# APPS.net
KiCad netlist of a schematic drawn in Altium Designer
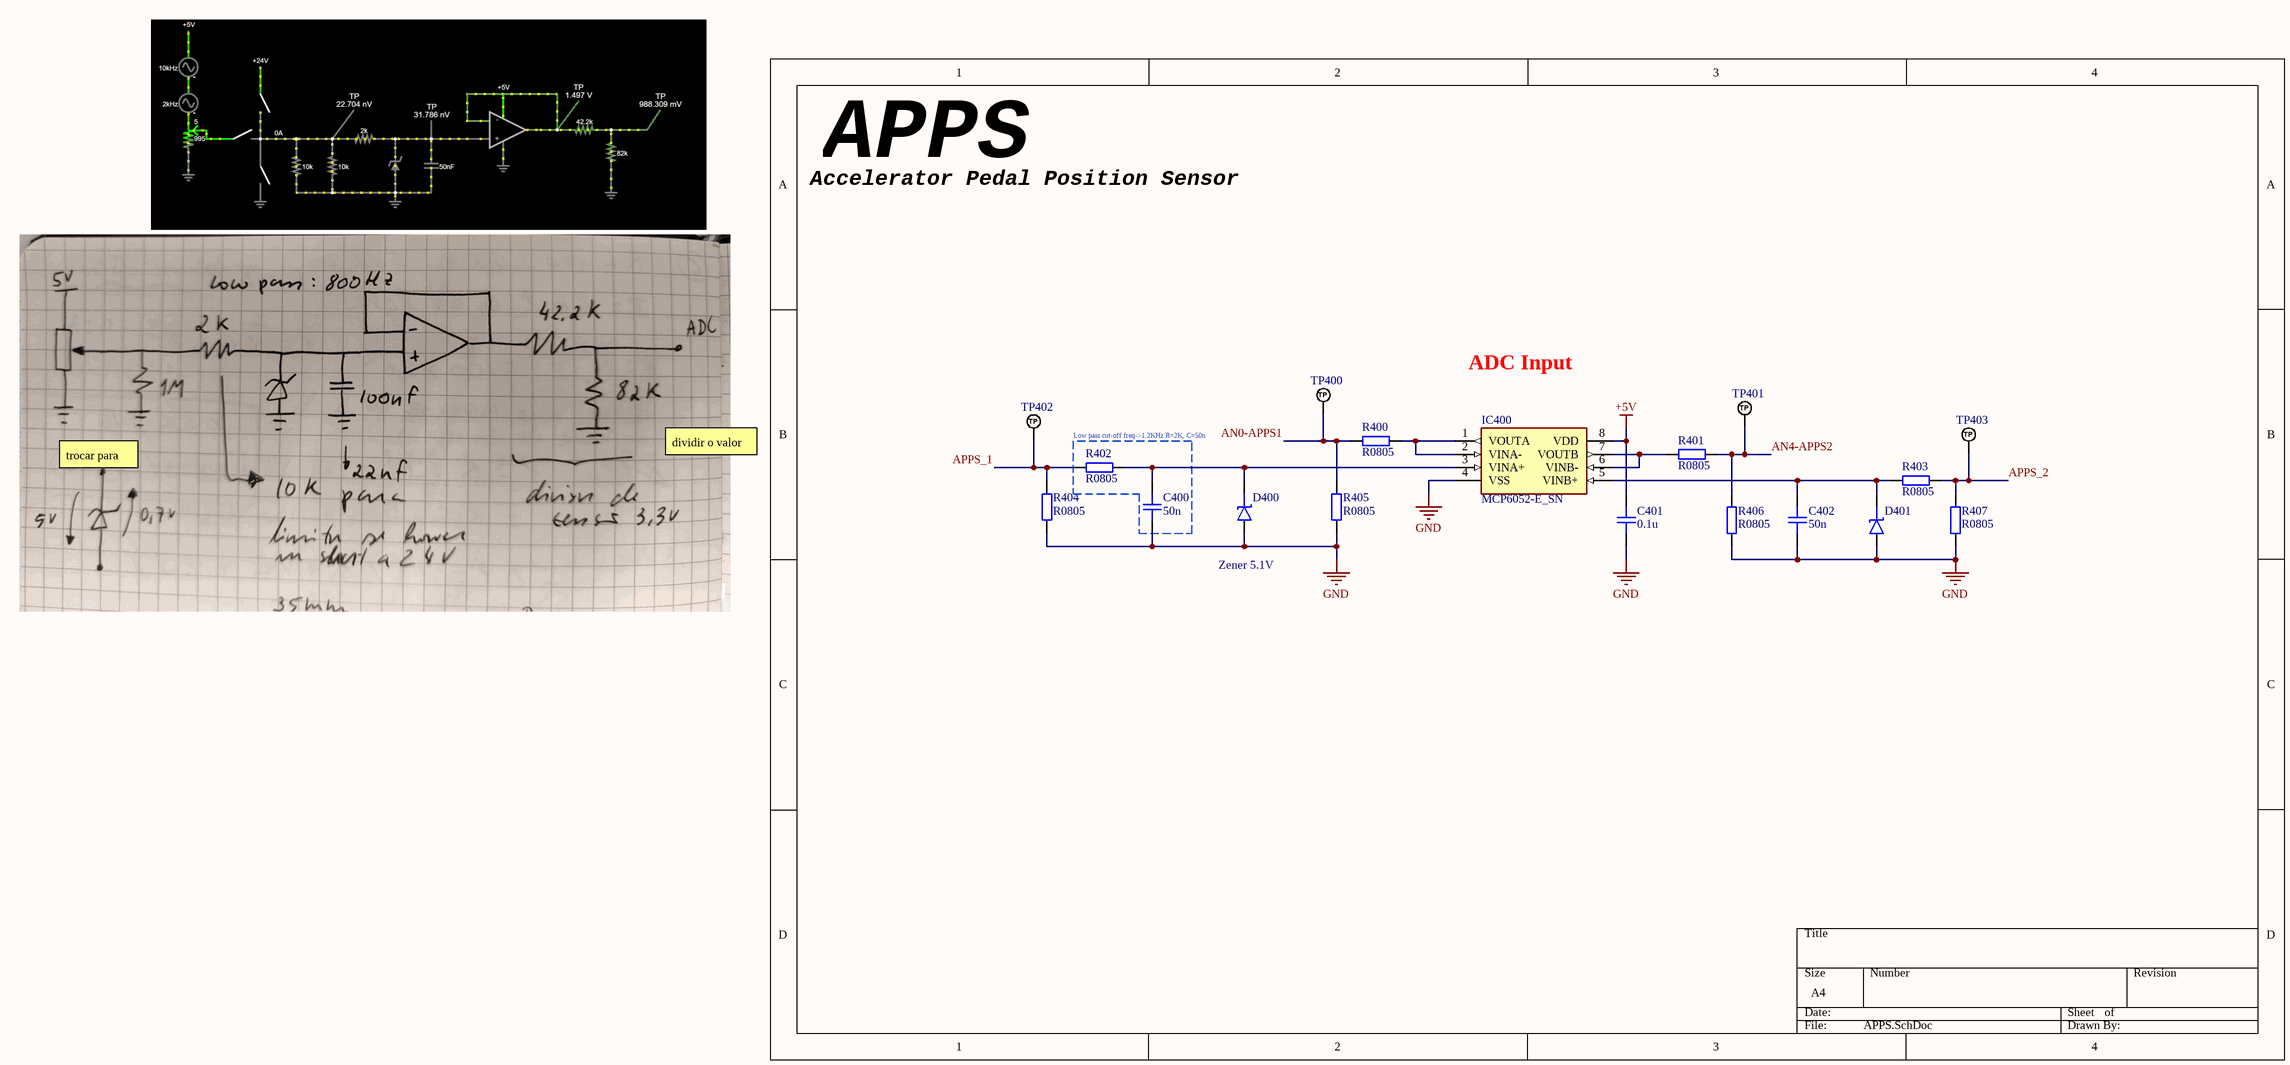
[diagram p0: APPS.SchDoc]

(export (version "E")
  (design (tool "Eeschema 10.0.6"))
  (components
    (comp (ref "C400")
      (value "50n")
      (footprint "CAP_0805")
      (description "Capacitor SMD 0805 10V")
      (libsource (lib "Schematic-Lib-PhilsLab") (part "CAP_0805_10V"))
    )
    (comp (ref "C401")
      (value "0.1u")
      (footprint "CAP_0805")
      (description "Capacitor SMD 0805 10V")
      (libsource (lib "Schematic-Lib-PhilsLab") (part "CAP_0805_10V"))
    )
    (comp (ref "C402")
      (value "50n")
      (footprint "CAP_0805")
      (description "Capacitor SMD 0805 10V")
      (libsource (lib "Schematic-Lib-PhilsLab") (part "CAP_0805_10V"))
    )
    (comp (ref "D400")
      (value "D_SCHOTTKY_SOD_323")
      (footprint "SOD-323")
      (description "Diode Schottky SMD SOD-323")
      (libsource (lib "PhilsLab") (part "D_SCHOTTKY_SOD_323"))
    )
    (comp (ref "D401")
      (value "D_SCHOTTKY_SOD_323")
      (footprint "SOD-323")
      (description "Diode Schottky SMD SOD-323")
      (libsource (lib "PhilsLab") (part "D_SCHOTTKY_SOD_323"))
    )
    (comp (ref "IC400")
      (value "MCP6052-E_SN")
      (footprint "Pedro_pcb_lib:SOIC127P600X175-8N")
      (description "Integrated Circuit")
      (fields
        (field (name "MANUFACTURER_PART_NUMBER") "MCP6052-E/SN")
        (field (name "MOUSER PART NUMBER") "579-MCP6052-E/SN")
      )
      (libsource (lib "*") (part "MCP6052-E_SN"))
    )
    (comp (ref "R400")
      (value "R0805")
      (footprint "RES_0805")
      (description "Resistor SMD 0805")
      (libsource (lib "Schematic-Lib-PhilsLab") (part "RES_0805"))
    )
    (comp (ref "R401")
      (value "R0805")
      (footprint "RES_0805")
      (description "Resistor SMD 0805")
      (libsource (lib "Schematic-Lib-PhilsLab") (part "RES_0805"))
    )
    (comp (ref "R402")
      (value "R0805")
      (footprint "RES_0805")
      (description "Resistor SMD 0805")
      (libsource (lib "Schematic-Lib-PhilsLab") (part "RES_0805"))
    )
    (comp (ref "R403")
      (value "R0805")
      (footprint "RES_0805")
      (description "Resistor SMD 0805")
      (libsource (lib "Schematic-Lib-PhilsLab") (part "RES_0805"))
    )
    (comp (ref "R404")
      (value "R0805")
      (footprint "RES_0805")
      (description "Resistor SMD 0805")
      (libsource (lib "Schematic-Lib-PhilsLab") (part "RES_0805"))
    )
    (comp (ref "R405")
      (value "R0805")
      (footprint "RES_0805")
      (description "Resistor SMD 0805")
      (libsource (lib "Schematic-Lib-PhilsLab") (part "RES_0805"))
    )
    (comp (ref "R406")
      (value "R0805")
      (footprint "RES_0805")
      (description "Resistor SMD 0805")
      (libsource (lib "Schematic-Lib-PhilsLab") (part "RES_0805"))
    )
    (comp (ref "R407")
      (value "R0805")
      (footprint "RES_0805")
      (description "Resistor SMD 0805")
      (libsource (lib "Schematic-Lib-PhilsLab") (part "RES_0805"))
    )
    (comp (ref "TP400")
      (value "TP_NOBOM")
      (footprint "PAD_RND_1MM")
      (description "Test Point Round 1mm (NO BOM)")
      (libsource (lib "Schematic-Lib-PhilsLab") (part "TEST_POINT_RND_1MM"))
    )
    (comp (ref "TP401")
      (value "TP_NOBOM")
      (footprint "PAD_RND_1MM")
      (description "Test Point Round 1mm (NO BOM)")
      (libsource (lib "Schematic-Lib-PhilsLab") (part "TEST_POINT_RND_1MM"))
    )
    (comp (ref "TP402")
      (value "TP_NOBOM")
      (footprint "PAD_RND_1MM")
      (description "Test Point Round 1mm (NO BOM)")
      (libsource (lib "Schematic-Lib-PhilsLab") (part "TEST_POINT_RND_1MM"))
    )
    (comp (ref "TP403")
      (value "TP_NOBOM")
      (footprint "PAD_RND_1MM")
      (description "Test Point Round 1mm (NO BOM)")
      (libsource (lib "Schematic-Lib-PhilsLab") (part "TEST_POINT_RND_1MM"))
    )
  )
  (nets
    (net (code "1") (name "+5V") (class "Default")
      (node (ref "C401") (pin "2") (pinfunction "2_2") (pintype "passive"))
      (node (ref "IC400") (pin "8") (pinfunction "VDD_8") (pintype "power_in"))
    )
    (net (code "2") (name "/AN0-APPS1") (class "Default")
      (node (ref "R400") (pin "2") (pinfunction "2_2") (pintype "passive"))
      (node (ref "R405") (pin "1") (pinfunction "1_1") (pintype "passive"))
      (node (ref "TP400") (pin "1") (pinfunction "TP_1") (pintype "passive"))
    )
    (net (code "3") (name "/AN4-APPS2") (class "Default")
      (node (ref "R401") (pin "1") (pinfunction "1_1") (pintype "passive"))
      (node (ref "R406") (pin "1") (pinfunction "1_1") (pintype "passive"))
      (node (ref "TP401") (pin "1") (pinfunction "TP_1") (pintype "passive"))
    )
    (net (code "4") (name "/APPS_1") (class "Default")
      (node (ref "R402") (pin "1") (pinfunction "1_1") (pintype "passive"))
      (node (ref "R404") (pin "2") (pinfunction "2_2") (pintype "passive"))
      (node (ref "TP402") (pin "1") (pinfunction "TP_1") (pintype "passive"))
    )
    (net (code "5") (name "/APPS_2") (class "Default")
      (node (ref "R403") (pin "2") (pinfunction "2_2") (pintype "passive"))
      (node (ref "R407") (pin "2") (pinfunction "2_2") (pintype "passive"))
      (node (ref "TP403") (pin "1") (pinfunction "TP_1") (pintype "passive"))
    )
    (net (code "6") (name "GND") (class "Default")
      (node (ref "C400") (pin "2") (pinfunction "2_2") (pintype "passive"))
      (node (ref "C401") (pin "1") (pinfunction "1_1") (pintype "passive"))
      (node (ref "C402") (pin "2") (pinfunction "2_2") (pintype "passive"))
      (node (ref "D400") (pin "A") (pinfunction "A_A") (pintype "passive"))
      (node (ref "D401") (pin "A") (pinfunction "A_A") (pintype "passive"))
      (node (ref "IC400") (pin "4") (pinfunction "VSS_4") (pintype "power_in"))
      (node (ref "R404") (pin "1") (pinfunction "1_1") (pintype "passive"))
      (node (ref "R405") (pin "2") (pinfunction "2_2") (pintype "passive"))
      (node (ref "R406") (pin "2") (pinfunction "2_2") (pintype "passive"))
      (node (ref "R407") (pin "1") (pinfunction "1_1") (pintype "passive"))
    )
    (net (code "7") (name "Net-(IC400-VINA+)") (class "Default")
      (node (ref "C400") (pin "1") (pinfunction "1_1") (pintype "passive"))
      (node (ref "D400") (pin "K") (pinfunction "K_K") (pintype "passive"))
      (node (ref "IC400") (pin "3") (pinfunction "VINA+_3") (pintype "input"))
      (node (ref "R402") (pin "2") (pinfunction "2_2") (pintype "passive"))
    )
    (net (code "8") (name "Net-(IC400-VINA-)") (class "Default")
      (node (ref "IC400") (pin "1") (pinfunction "VOUTA_1") (pintype "output"))
      (node (ref "IC400") (pin "2") (pinfunction "VINA-_2") (pintype "input"))
      (node (ref "R400") (pin "1") (pinfunction "1_1") (pintype "passive"))
    )
    (net (code "9") (name "Net-(IC400-VINB+)") (class "Default")
      (node (ref "C402") (pin "1") (pinfunction "1_1") (pintype "passive"))
      (node (ref "D401") (pin "K") (pinfunction "K_K") (pintype "passive"))
      (node (ref "IC400") (pin "5") (pinfunction "VINB+_5") (pintype "input"))
      (node (ref "R403") (pin "1") (pinfunction "1_1") (pintype "passive"))
    )
    (net (code "10") (name "Net-(IC400-VINB-)") (class "Default")
      (node (ref "IC400") (pin "6") (pinfunction "VINB-_6") (pintype "input"))
      (node (ref "IC400") (pin "7") (pinfunction "VOUTB_7") (pintype "output"))
      (node (ref "R401") (pin "2") (pinfunction "2_2") (pintype "passive"))
    )
  )
)
